# nRF52832_MCU.net
KiCad netlist of a schematic drawn in Altium Designer
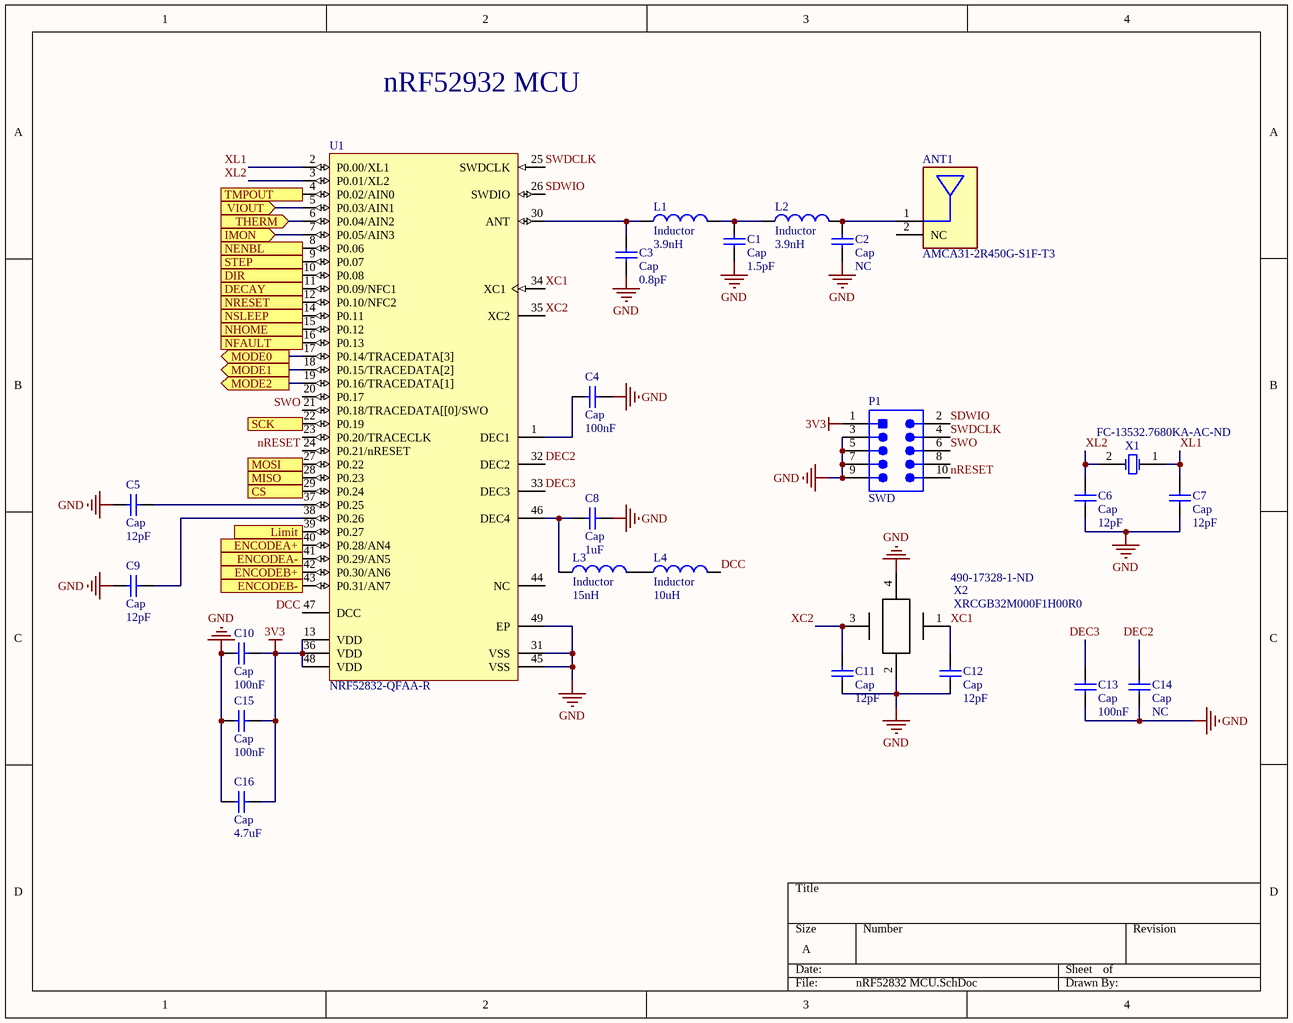
[diagram p0: nRF52832 MCU.SchDoc]

(export (version "E")
  (design (tool "Eeschema 10.0.6"))
  (components
    (comp (ref "ANT1")
      (value "AMCA31-2R450G-S1F-T3")
      (footprint "FP-AMCA31-MFG")
      (description "RF ANT 2.4GHZ CHIP SOLDER SMD")
      (fields
        (field (name "OCTOPART") "https://octopart.com/amca31-2r450g-s1f-t3-abracon-31435383")
        (field (name "MANUFACTURER") "Abracon")
      )
      (libsource (lib "Altium Content Vault") (part "feefd54aed95757a858c12fc87bd8d5"))
    )
    (comp (ref "C1")
      (value "Cap")
      (footprint "0402-A")
      (description "Capacitor")
      (fields (field (name "ALTIUM_VALUE") "1.5pF") (field (name "PUBLISHER") "Altium Limited"))
      (libsource (lib "Miscellaneous Devices") (part "Cap"))
    )
    (comp (ref "C2")
      (value "Cap")
      (footprint "0402-A")
      (description "Capacitor")
      (fields (field (name "ALTIUM_VALUE") "NC") (field (name "PUBLISHER") "Altium Limited"))
      (libsource (lib "Miscellaneous Devices") (part "Cap"))
    )
    (comp (ref "C3")
      (value "Cap")
      (footprint "0402-A")
      (description "Capacitor")
      (fields (field (name "ALTIUM_VALUE") "0.8pF") (field (name "PUBLISHER") "Altium Limited"))
      (libsource (lib "Miscellaneous Devices") (part "Cap"))
    )
    (comp (ref "C4")
      (value "Cap")
      (footprint "1608[0603]")
      (description "Capacitor")
      (fields (field (name "ALTIUM_VALUE") "100nF") (field (name "PUBLISHER") "Altium Limited"))
      (libsource (lib "Miscellaneous Devices") (part "Cap"))
    )
    (comp (ref "C5")
      (value "Cap")
      (footprint "0402-A")
      (description "Capacitor")
      (fields (field (name "ALTIUM_VALUE") "12pF") (field (name "PUBLISHER") "Altium Limited"))
      (libsource (lib "Miscellaneous Devices") (part "Cap"))
    )
    (comp (ref "C6")
      (value "Cap")
      (footprint "0402-A")
      (description "Capacitor")
      (fields (field (name "ALTIUM_VALUE") "12pF") (field (name "PUBLISHER") "Altium Limited"))
      (libsource (lib "Miscellaneous Devices") (part "Cap"))
    )
    (comp (ref "C7")
      (value "Cap")
      (footprint "0402-A")
      (description "Capacitor")
      (fields (field (name "ALTIUM_VALUE") "12pF") (field (name "PUBLISHER") "Altium Limited"))
      (libsource (lib "Miscellaneous Devices") (part "Cap"))
    )
    (comp (ref "C8")
      (value "Cap")
      (footprint "1608[0603]")
      (description "Capacitor")
      (fields (field (name "ALTIUM_VALUE") "1uF") (field (name "PUBLISHER") "Altium Limited"))
      (libsource (lib "Miscellaneous Devices") (part "Cap"))
    )
    (comp (ref "C9")
      (value "Cap")
      (footprint "0402-A")
      (description "Capacitor")
      (fields (field (name "ALTIUM_VALUE") "12pF") (field (name "PUBLISHER") "Altium Limited"))
      (libsource (lib "Miscellaneous Devices") (part "Cap"))
    )
    (comp (ref "C10")
      (value "Cap")
      (footprint "1608[0603]")
      (description "Capacitor")
      (fields (field (name "ALTIUM_VALUE") "100nF") (field (name "PUBLISHER") "Altium Limited"))
      (libsource (lib "Miscellaneous Devices") (part "Cap"))
    )
    (comp (ref "C11")
      (value "Cap")
      (footprint "0402-A")
      (description "Capacitor")
      (fields (field (name "ALTIUM_VALUE") "12pF") (field (name "PUBLISHER") "Altium Limited"))
      (libsource (lib "Miscellaneous Devices") (part "Cap"))
    )
    (comp (ref "C12")
      (value "Cap")
      (footprint "0402-A")
      (description "Capacitor")
      (fields (field (name "ALTIUM_VALUE") "12pF") (field (name "PUBLISHER") "Altium Limited"))
      (libsource (lib "Miscellaneous Devices") (part "Cap"))
    )
    (comp (ref "C13")
      (value "Cap")
      (footprint "1608[0603]")
      (description "Capacitor")
      (fields (field (name "ALTIUM_VALUE") "100nF") (field (name "PUBLISHER") "Altium Limited"))
      (libsource (lib "Miscellaneous Devices") (part "Cap"))
    )
    (comp (ref "C14")
      (value "Cap")
      (footprint "0402-A")
      (description "Capacitor")
      (fields (field (name "ALTIUM_VALUE") "NC") (field (name "PUBLISHER") "Altium Limited"))
      (libsource (lib "Miscellaneous Devices") (part "Cap"))
    )
    (comp (ref "C15")
      (value "Cap")
      (footprint "1608[0603]")
      (description "Capacitor")
      (fields (field (name "ALTIUM_VALUE") "100nF") (field (name "PUBLISHER") "Altium Limited"))
      (libsource (lib "Miscellaneous Devices") (part "Cap"))
    )
    (comp (ref "C16")
      (value "Cap")
      (footprint "6-0805_M")
      (description "Capacitor")
      (fields (field (name "ALTIUM_VALUE") "4.7uF") (field (name "PUBLISHER") "Altium Limited"))
      (libsource (lib "Miscellaneous Devices") (part "Cap"))
    )
    (comp (ref "L1")
      (value "Inductor")
      (footprint "0402-A")
      (fields (field (name "ALTIUM_VALUE") "3.9nH") (field (name "PUBLISHER") "Altium Limited"))
      (libsource (lib "Miscellaneous Devices") (part "Inductor"))
    )
    (comp (ref "L2")
      (value "Inductor")
      (footprint "0402-A")
      (fields (field (name "ALTIUM_VALUE") "3.9nH") (field (name "PUBLISHER") "Altium Limited"))
      (libsource (lib "Miscellaneous Devices") (part "Inductor"))
    )
    (comp (ref "L3")
      (value "Inductor")
      (footprint "0402-A")
      (fields (field (name "ALTIUM_VALUE") "15nH") (field (name "PUBLISHER") "Altium Limited"))
      (libsource (lib "Miscellaneous Devices") (part "Inductor"))
    )
    (comp (ref "L4")
      (value "Inductor")
      (footprint "1608[0603]")
      (fields (field (name "ALTIUM_VALUE") "10uH") (field (name "PUBLISHER") "Altium Limited"))
      (libsource (lib "Miscellaneous Devices") (part "Inductor"))
    )
    (comp (ref "P1")
      (value "SWD")
      (footprint "SMTC-FTSH-105-01-L-DV-K_V")
      (description "Male Header, Pitch 1.27 mm, 2 x 5 Position, Height 6.25 mm")
      (fields (field (name "MANUFACTURER") "Samtec"))
      (libsource (lib "Altium Content Vault") (part "CN-2P-M-R10"))
    )
    (comp (ref "U1")
      (value "NRF52832-QFAA-R")
      (footprint "NRSC-QF-48_M")
      (fields (field (name "MANUFACTURER") "Nordic Semiconductor"))
      (libsource (lib "Altium Content Vault") (part "NRSC-NRF52832-QF-48"))
    )
    (comp (ref "X1")
      (value "FC-135 32.7680KA-AC")
      (footprint "FC-13532.7680KA-AC-ND")
      (description "32.768kHz Crystal Oscillator")
      (fields
        (field (name "SUPPLIER PART NUMBER 1") "FC-13532.7680KA-AC-ND")
        (field (name "PUBLISHER") "Altium Limited")
      )
      (libsource (lib "Miscellaneous Devices") (part "XTAL"))
    )
    (comp (ref "X2")
      (value "XRCGB32M000F1H00R0")
      (footprint "XRCGB32M000F1H00R0")
      (description "32MHz Crystal Oscillator")
      (fields (field (name "SUPPLIER PART NUMBER 1") "490-17328-1-ND"))
      (libsource (lib "XRCGB32M000F1H00R0") (part "XRCGB32M000F1H00R0"))
    )
  )
  (nets
    (net (code "1") (name "/CS") (class "Default")
      (node (ref "U1") (pin "29") (pinfunction "P0.24_29") (pintype "bidirectional"))
    )
    (net (code "2") (name "/DCC") (class "Default")
      (node (ref "L4") (pin "2") (pinfunction "2_2") (pintype "passive"))
      (node (ref "U1") (pin "47") (pinfunction "DCC_47") (pintype "power_in"))
    )
    (net (code "3") (name "/DEC2") (class "Default")
      (node (ref "C14") (pin "1") (pinfunction "1_1") (pintype "passive"))
      (node (ref "U1") (pin "32") (pinfunction "DEC2_32") (pintype "passive"))
    )
    (net (code "4") (name "/DEC3") (class "Default")
      (node (ref "C13") (pin "1") (pinfunction "1_1") (pintype "passive"))
      (node (ref "U1") (pin "33") (pinfunction "DEC3_33") (pintype "passive"))
    )
    (net (code "5") (name "/DECAY") (class "Default")
      (node (ref "U1") (pin "11") (pinfunction "P0.09/NFC1_11") (pintype "bidirectional"))
    )
    (net (code "6") (name "/DIR") (class "Default")
      (node (ref "U1") (pin "10") (pinfunction "P0.08_10") (pintype "bidirectional"))
    )
    (net (code "7") (name "/ENCODEA+") (class "Default")
      (node (ref "U1") (pin "40") (pinfunction "P0.28/AN4_40") (pintype "bidirectional"))
    )
    (net (code "8") (name "/ENCODEA-") (class "Default")
      (node (ref "U1") (pin "41") (pinfunction "P0.29/AN5_41") (pintype "bidirectional"))
    )
    (net (code "9") (name "/ENCODEB+") (class "Default")
      (node (ref "U1") (pin "42") (pinfunction "P0.30/AN6_42") (pintype "bidirectional"))
    )
    (net (code "10") (name "/ENCODEB-") (class "Default")
      (node (ref "U1") (pin "43") (pinfunction "P0.31/AN7_43") (pintype "bidirectional"))
    )
    (net (code "11") (name "/IMON") (class "Default")
      (node (ref "U1") (pin "7") (pinfunction "P0.05/AIN3_7") (pintype "bidirectional"))
    )
    (net (code "12") (name "/Limit") (class "Default")
      (node (ref "U1") (pin "39") (pinfunction "P0.27_39") (pintype "bidirectional"))
    )
    (net (code "13") (name "/MISO") (class "Default")
      (node (ref "U1") (pin "28") (pinfunction "P0.23_28") (pintype "bidirectional"))
    )
    (net (code "14") (name "/MODE0") (class "Default")
      (node (ref "U1") (pin "17") (pinfunction "P0.14/TRACEDATA[3]_17") (pintype "bidirectional"))
    )
    (net (code "15") (name "/MODE1") (class "Default")
      (node (ref "U1") (pin "18") (pinfunction "P0.15/TRACEDATA[2]_18") (pintype "bidirectional"))
    )
    (net (code "16") (name "/MODE2") (class "Default")
      (node (ref "U1") (pin "19") (pinfunction "P0.16/TRACEDATA[1]_19") (pintype "bidirectional"))
    )
    (net (code "17") (name "/MOSI") (class "Default")
      (node (ref "U1") (pin "27") (pinfunction "P0.22_27") (pintype "bidirectional"))
    )
    (net (code "18") (name "/NENBL") (class "Default")
      (node (ref "U1") (pin "8") (pinfunction "P0.06_8") (pintype "bidirectional"))
    )
    (net (code "19") (name "/NFAULT") (class "Default")
      (node (ref "U1") (pin "16") (pinfunction "P0.13_16") (pintype "bidirectional"))
    )
    (net (code "20") (name "/NHOME") (class "Default")
      (node (ref "U1") (pin "15") (pinfunction "P0.12_15") (pintype "bidirectional"))
    )
    (net (code "21") (name "/NRESET") (class "Default")
      (node (ref "U1") (pin "12") (pinfunction "P0.10/NFC2_12") (pintype "bidirectional"))
    )
    (net (code "22") (name "/NSLEEP") (class "Default")
      (node (ref "U1") (pin "14") (pinfunction "P0.11_14") (pintype "bidirectional"))
    )
    (net (code "23") (name "/SCK") (class "Default")
      (node (ref "U1") (pin "22") (pinfunction "P0.19_22") (pintype "bidirectional"))
    )
    (net (code "24") (name "/SDWIO") (class "Default")
      (node (ref "P1") (pin "2") (pinfunction "2_2") (pintype "passive"))
      (node (ref "U1") (pin "26") (pinfunction "SWDIO_26") (pintype "bidirectional"))
    )
    (net (code "25") (name "/STEP") (class "Default")
      (node (ref "U1") (pin "9") (pinfunction "P0.07_9") (pintype "bidirectional"))
    )
    (net (code "26") (name "/SWDCLK") (class "Default")
      (node (ref "P1") (pin "4") (pinfunction "4_4") (pintype "passive"))
      (node (ref "U1") (pin "25") (pinfunction "SWDCLK_25") (pintype "input"))
    )
    (net (code "27") (name "/SWO") (class "Default")
      (node (ref "P1") (pin "6") (pinfunction "6_6") (pintype "passive"))
      (node (ref "U1") (pin "21") (pinfunction "P0.18/TRACEDATA[[0]/SWO_21") (pintype "bidirectional"))
    )
    (net (code "28") (name "/THERM") (class "Default")
      (node (ref "U1") (pin "6") (pinfunction "P0.04/AIN2_6") (pintype "bidirectional"))
    )
    (net (code "29") (name "/TMPOUT") (class "Default")
      (node (ref "U1") (pin "4") (pinfunction "P0.02/AIN0_4") (pintype "bidirectional"))
    )
    (net (code "30") (name "/VIOUT") (class "Default")
      (node (ref "U1") (pin "5") (pinfunction "P0.03/AIN1_5") (pintype "bidirectional"))
    )
    (net (code "31") (name "/XC1") (class "Default")
      (node (ref "C12") (pin "2") (pinfunction "2_2") (pintype "passive"))
      (node (ref "U1") (pin "34") (pinfunction "XC1_34") (pintype "input"))
      (node (ref "X2") (pin "1") (pinfunction "1_1") (pintype "passive"))
    )
    (net (code "32") (name "/XC2") (class "Default")
      (node (ref "C11") (pin "2") (pinfunction "2_2") (pintype "passive"))
      (node (ref "U1") (pin "35") (pinfunction "XC2_35") (pintype "passive"))
      (node (ref "X2") (pin "3") (pintype "passive"))
    )
    (net (code "33") (name "/XL1") (class "Default")
      (node (ref "C7") (pin "2") (pinfunction "2_2") (pintype "passive"))
      (node (ref "U1") (pin "2") (pinfunction "P0.00/XL1_2") (pintype "bidirectional"))
      (node (ref "X1") (pin "1") (pinfunction "OSC1_1") (pintype "passive"))
    )
    (net (code "34") (name "/XL2") (class "Default")
      (node (ref "C6") (pin "2") (pinfunction "2_2") (pintype "passive"))
      (node (ref "U1") (pin "3") (pinfunction "P0.01/XL2_3") (pintype "bidirectional"))
      (node (ref "X1") (pin "2") (pinfunction "OSC2_2") (pintype "passive"))
    )
    (net (code "35") (name "/nRESET") (class "Default")
      (node (ref "P1") (pin "10") (pinfunction "10_10") (pintype "passive"))
      (node (ref "U1") (pin "24") (pinfunction "P0.21/nRESET_24") (pintype "bidirectional"))
    )
    (net (code "36") (name "3V3") (class "Default")
      (node (ref "C10") (pin "1") (pinfunction "1_1") (pintype "passive"))
      (node (ref "C15") (pin "1") (pinfunction "1_1") (pintype "passive"))
      (node (ref "C16") (pin "1") (pinfunction "1_1") (pintype "passive"))
      (node (ref "P1") (pin "1") (pinfunction "1_1") (pintype "passive"))
      (node (ref "U1") (pin "13") (pinfunction "VDD_13") (pintype "power_in"))
      (node (ref "U1") (pin "36") (pinfunction "VDD_36") (pintype "power_in"))
      (node (ref "U1") (pin "48") (pinfunction "VDD_48") (pintype "power_in"))
    )
    (net (code "37") (name "GND") (class "Default")
      (node (ref "C1") (pin "1") (pinfunction "1_1") (pintype "passive"))
      (node (ref "C10") (pin "2") (pinfunction "2_2") (pintype "passive"))
      (node (ref "C11") (pin "1") (pinfunction "1_1") (pintype "passive"))
      (node (ref "C12") (pin "1") (pinfunction "1_1") (pintype "passive"))
      (node (ref "C13") (pin "2") (pinfunction "2_2") (pintype "passive"))
      (node (ref "C14") (pin "2") (pinfunction "2_2") (pintype "passive"))
      (node (ref "C15") (pin "2") (pinfunction "2_2") (pintype "passive"))
      (node (ref "C16") (pin "2") (pinfunction "2_2") (pintype "passive"))
      (node (ref "C2") (pin "1") (pinfunction "1_1") (pintype "passive"))
      (node (ref "C3") (pin "1") (pinfunction "1_1") (pintype "passive"))
      (node (ref "C4") (pin "1") (pinfunction "1_1") (pintype "passive"))
      (node (ref "C5") (pin "2") (pinfunction "2_2") (pintype "passive"))
      (node (ref "C6") (pin "1") (pinfunction "1_1") (pintype "passive"))
      (node (ref "C7") (pin "1") (pinfunction "1_1") (pintype "passive"))
      (node (ref "C8") (pin "1") (pinfunction "1_1") (pintype "passive"))
      (node (ref "C9") (pin "2") (pinfunction "2_2") (pintype "passive"))
      (node (ref "P1") (pin "3") (pinfunction "3_3") (pintype "passive"))
      (node (ref "P1") (pin "5") (pinfunction "5_5") (pintype "passive"))
      (node (ref "P1") (pin "7") (pinfunction "7_7") (pintype "passive"))
      (node (ref "P1") (pin "9") (pinfunction "9_9") (pintype "passive"))
      (node (ref "U1") (pin "31") (pinfunction "VSS_31") (pintype "power_in"))
      (node (ref "U1") (pin "45") (pinfunction "VSS_45") (pintype "power_in"))
      (node (ref "U1") (pin "49") (pinfunction "EP_49") (pintype "power_in"))
      (node (ref "X2") (pin "2") (pinfunction "3_2") (pintype "passive"))
      (node (ref "X2") (pin "4") (pinfunction "4_4") (pintype "passive"))
    )
    (net (code "38") (name "Net-(ANT1-Feed_Point)") (class "Default")
      (node (ref "ANT1") (pin "1") (pinfunction "Feed_Point_1") (pintype "passive"))
      (node (ref "C2") (pin "2") (pinfunction "2_2") (pintype "passive"))
      (node (ref "L2") (pin "2") (pinfunction "2_2") (pintype "passive"))
    )
    (net (code "39") (name "Net-(C1-Pad2)") (class "Default")
      (node (ref "C1") (pin "2") (pinfunction "2_2") (pintype "passive"))
      (node (ref "L1") (pin "2") (pinfunction "2_2") (pintype "passive"))
      (node (ref "L2") (pin "1") (pinfunction "1_1") (pintype "passive"))
    )
    (net (code "40") (name "Net-(L3-Pad2)") (class "Default")
      (node (ref "L3") (pin "2") (pinfunction "2_2") (pintype "passive"))
      (node (ref "L4") (pin "1") (pinfunction "1_1") (pintype "passive"))
    )
    (net (code "41") (name "Net-(U1-ANT)") (class "Default")
      (node (ref "C3") (pin "2") (pinfunction "2_2") (pintype "passive"))
      (node (ref "L1") (pin "1") (pinfunction "1_1") (pintype "passive"))
      (node (ref "U1") (pin "30") (pinfunction "ANT_30") (pintype "bidirectional"))
    )
    (net (code "42") (name "Net-(U1-DEC1)") (class "Default")
      (node (ref "C4") (pin "2") (pinfunction "2_2") (pintype "passive"))
      (node (ref "U1") (pin "1") (pinfunction "DEC1_1") (pintype "passive"))
    )
    (net (code "43") (name "Net-(U1-DEC4)") (class "Default")
      (node (ref "C8") (pin "2") (pinfunction "2_2") (pintype "passive"))
      (node (ref "L3") (pin "1") (pinfunction "1_1") (pintype "passive"))
      (node (ref "U1") (pin "46") (pinfunction "DEC4_46") (pintype "passive"))
    )
    (net (code "44") (name "Net-(U1-P0.25)") (class "Default")
      (node (ref "C5") (pin "1") (pinfunction "1_1") (pintype "passive"))
      (node (ref "U1") (pin "37") (pinfunction "P0.25_37") (pintype "bidirectional"))
    )
    (net (code "45") (name "Net-(U1-P0.26)") (class "Default")
      (node (ref "C9") (pin "1") (pinfunction "1_1") (pintype "passive"))
      (node (ref "U1") (pin "38") (pinfunction "P0.26_38") (pintype "bidirectional"))
    )
    (net (code "46") (name "unconnected-(ANT1-NC-Pad2)") (class "Default")
      (node (ref "ANT1") (pin "2") (pinfunction "NC_2") (pintype "passive"))
    )
    (net (code "47") (name "unconnected-(P1-Pad8)") (class "Default")
      (node (ref "P1") (pin "8") (pinfunction "8_8") (pintype "passive"))
    )
    (net (code "48") (name "unconnected-(U1-NC-Pad44)") (class "Default")
      (node (ref "U1") (pin "44") (pinfunction "NC_44") (pintype "passive"))
    )
    (net (code "49") (name "unconnected-(U1-P0.17-Pad20)") (class "Default")
      (node (ref "U1") (pin "20") (pinfunction "P0.17_20") (pintype "bidirectional"))
    )
    (net (code "50") (name "unconnected-(U1-P0.20{slash}TRACECLK-Pad23)") (class "Default")
      (node (ref "U1") (pin "23") (pinfunction "P0.20/TRACECLK_23") (pintype "bidirectional"))
    )
  )
)
